# newimu.net
KiCad netlist of a schematic drawn in EAGLE
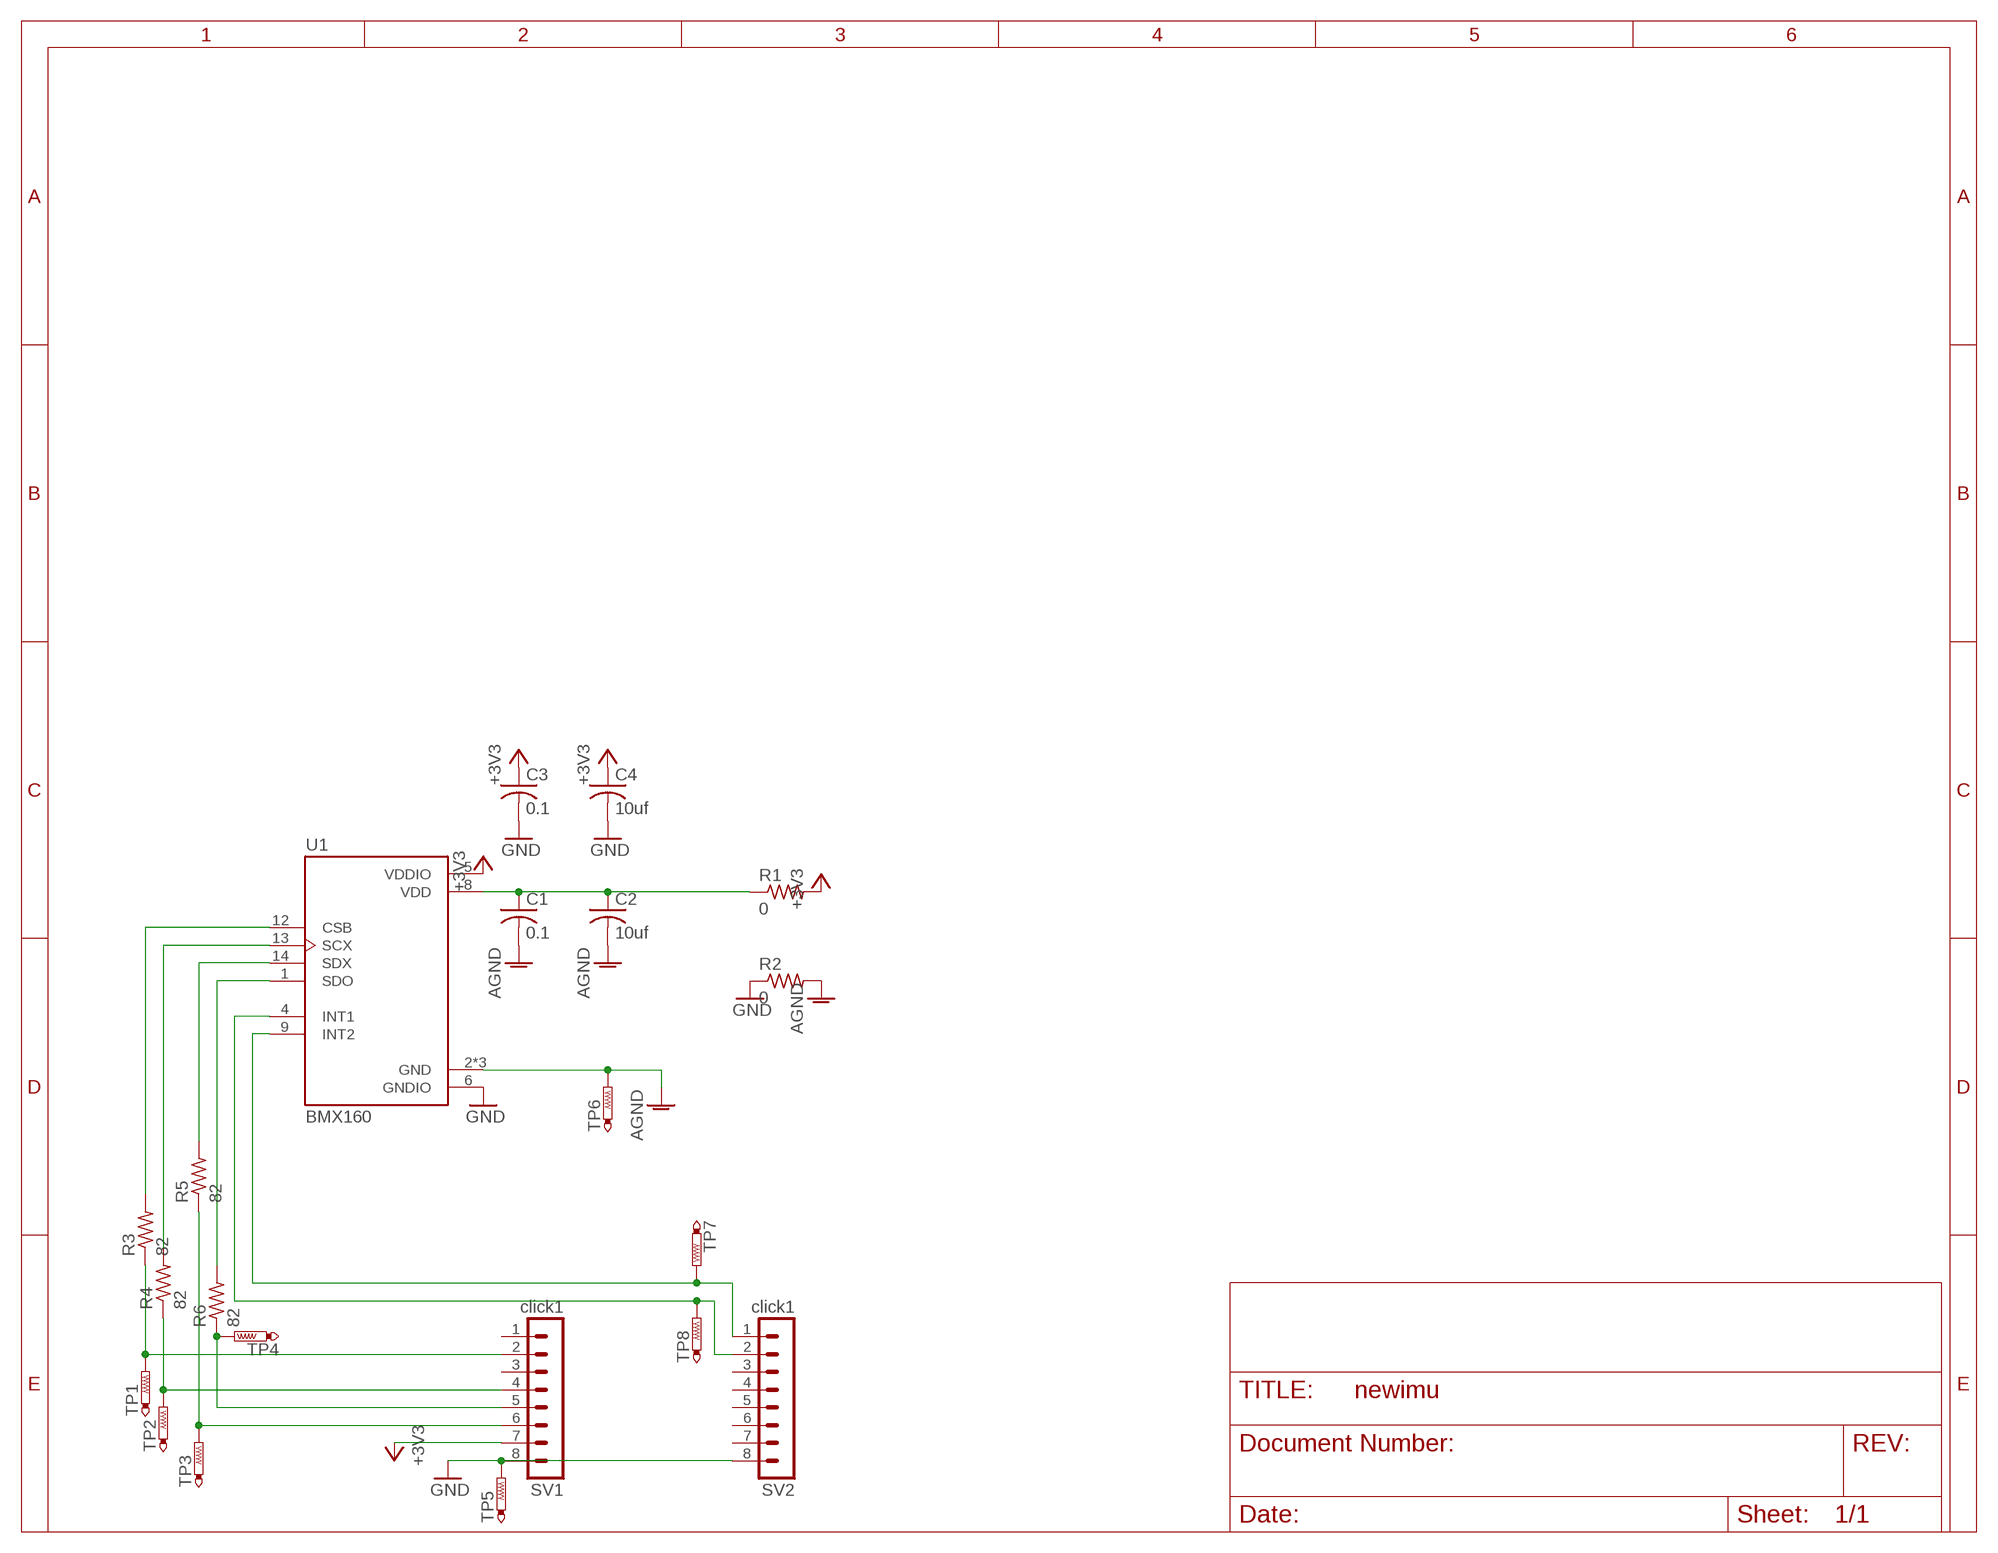
[diagram p0: schematic, sheet 1]

(export (version "E")
  (design (tool "Eeschema 10.0.6"))
  (components
    (comp (ref "C1")
      (value "0.1")
      (footprint "eagle-import:C0805")
      (libsource (lib "eagle-import") (part "C-USC0805"))
    )
    (comp (ref "C2")
      (value "10uf")
      (footprint "eagle-import:C0805")
      (libsource (lib "eagle-import") (part "C-USC0805"))
    )
    (comp (ref "C3")
      (value "0.1")
      (footprint "eagle-import:C0805")
      (libsource (lib "eagle-import") (part "C-USC0805"))
    )
    (comp (ref "C4")
      (value "10uf")
      (footprint "eagle-import:C0805")
      (libsource (lib "eagle-import") (part "C-USC0805"))
    )
    (comp (ref "R1")
      (value "0")
      (footprint "eagle-import:M0805")
      (libsource (lib "eagle-import") (part "R-US_M0805"))
    )
    (comp (ref "R2")
      (value "0")
      (footprint "eagle-import:M0805")
      (libsource (lib "eagle-import") (part "R-US_M0805"))
    )
    (comp (ref "R3")
      (value "82")
      (footprint "eagle-import:M0805")
      (libsource (lib "eagle-import") (part "R-US_M0805"))
    )
    (comp (ref "R4")
      (value "82")
      (footprint "eagle-import:M0805")
      (libsource (lib "eagle-import") (part "R-US_M0805"))
    )
    (comp (ref "R5")
      (value "82")
      (footprint "eagle-import:M0805")
      (libsource (lib "eagle-import") (part "R-US_M0805"))
    )
    (comp (ref "R6")
      (value "82")
      (footprint "eagle-import:M0805")
      (libsource (lib "eagle-import") (part "R-US_M0805"))
    )
    (comp (ref "SV1")
      (value "click1")
      (footprint "eagle-import:MA08-1")
      (libsource (lib "eagle-import") (part "MA08-1"))
    )
    (comp (ref "SV2")
      (value "click1")
      (footprint "eagle-import:MA08-1")
      (libsource (lib "eagle-import") (part "MA08-1"))
    )
    (comp (ref "TP1")
      (value "PTR1B1,27")
      (footprint "eagle-import:B1,27")
      (libsource (lib "eagle-import") (part "PTR1B1,27"))
    )
    (comp (ref "TP2")
      (value "PTR1B1,27")
      (footprint "eagle-import:B1,27")
      (libsource (lib "eagle-import") (part "PTR1B1,27"))
    )
    (comp (ref "TP3")
      (value "PTR1B1,27")
      (footprint "eagle-import:B1,27")
      (libsource (lib "eagle-import") (part "PTR1B1,27"))
    )
    (comp (ref "TP4")
      (value "PTR1B1,27")
      (footprint "eagle-import:B1,27")
      (libsource (lib "eagle-import") (part "PTR1B1,27"))
    )
    (comp (ref "TP5")
      (value "PTR1B1,27")
      (footprint "eagle-import:B1,27")
      (libsource (lib "eagle-import") (part "PTR1B1,27"))
    )
    (comp (ref "TP6")
      (value "PTR1B1,27")
      (footprint "eagle-import:B1,27")
      (libsource (lib "eagle-import") (part "PTR1B1,27"))
    )
    (comp (ref "TP7")
      (value "PTR1B1,27")
      (footprint "eagle-import:B1,27")
      (libsource (lib "eagle-import") (part "PTR1B1,27"))
    )
    (comp (ref "TP8")
      (value "PTR1B1,27")
      (footprint "eagle-import:B1,27")
      (libsource (lib "eagle-import") (part "PTR1B1,27"))
    )
    (comp (ref "U1")
      (value "BMX160")
      (footprint "eagle-import:PQFN50P250X300X100-14N")
      (fields (field (name "MF") "Bosch Sensortec"))
      (libsource (lib "eagle-import") (part "BMX160"))
    )
  )
  (nets
    (net (code "1") (name "+3V3") (class "Default")
      (node (ref "C3") (pin "1") (pinfunction "1_1") (pintype "passive"))
      (node (ref "C4") (pin "1") (pinfunction "1_1") (pintype "passive"))
      (node (ref "R1") (pin "2") (pinfunction "2_2") (pintype "passive"))
      (node (ref "SV1") (pin "7") (pinfunction "7_7") (pintype "passive"))
      (node (ref "U1") (pin "5") (pinfunction "VDDIO_5") (pintype "power_in"))
    )
    (net (code "2") (name "AGND") (class "Default")
      (node (ref "C1") (pin "2") (pinfunction "2_2") (pintype "passive"))
      (node (ref "C2") (pin "2") (pinfunction "2_2") (pintype "passive"))
      (node (ref "R2") (pin "2") (pinfunction "2_2") (pintype "passive"))
      (node (ref "TP6") (pin "TP") (pinfunction "TP_TP") (pintype "input"))
      (node (ref "U1") (pin "2") (pinfunction "GND_2") (pintype "power_in"))
      (node (ref "U1") (pin "3") (pinfunction "GND_3") (pintype "power_in"))
      (node (ref "U1") (pin "7") (pinfunction "GND_7") (pintype "power_in"))
    )
    (net (code "3") (name "GND") (class "Default")
      (node (ref "C3") (pin "2") (pinfunction "2_2") (pintype "passive"))
      (node (ref "C4") (pin "2") (pinfunction "2_2") (pintype "passive"))
      (node (ref "R2") (pin "1") (pinfunction "1_1") (pintype "passive"))
      (node (ref "SV1") (pin "8") (pinfunction "8_8") (pintype "passive"))
      (node (ref "SV2") (pin "8") (pinfunction "8_8") (pintype "passive"))
      (node (ref "TP5") (pin "TP") (pinfunction "TP_TP") (pintype "input"))
      (node (ref "U1") (pin "6") (pinfunction "GNDIO_6") (pintype "power_in"))
    )
    (net (code "4") (name "Net-(R3-Pad1)") (class "Default")
      (node (ref "R3") (pin "1") (pinfunction "1_1") (pintype "passive"))
      (node (ref "SV1") (pin "2") (pinfunction "2_2") (pintype "passive"))
      (node (ref "TP1") (pin "TP") (pinfunction "TP_TP") (pintype "input"))
    )
    (net (code "5") (name "Net-(R4-Pad1)") (class "Default")
      (node (ref "R4") (pin "1") (pinfunction "1_1") (pintype "passive"))
      (node (ref "SV1") (pin "4") (pinfunction "4_4") (pintype "passive"))
      (node (ref "TP2") (pin "TP") (pinfunction "TP_TP") (pintype "input"))
    )
    (net (code "6") (name "Net-(R5-Pad1)") (class "Default")
      (node (ref "R5") (pin "1") (pinfunction "1_1") (pintype "passive"))
      (node (ref "SV1") (pin "6") (pinfunction "6_6") (pintype "passive"))
      (node (ref "TP3") (pin "TP") (pinfunction "TP_TP") (pintype "input"))
    )
    (net (code "7") (name "Net-(R6-Pad1)") (class "Default")
      (node (ref "R6") (pin "1") (pinfunction "1_1") (pintype "passive"))
      (node (ref "SV1") (pin "5") (pinfunction "5_5") (pintype "passive"))
      (node (ref "TP4") (pin "TP") (pinfunction "TP_TP") (pintype "input"))
    )
    (net (code "8") (name "Net-(U1-CSB)") (class "Default")
      (node (ref "R3") (pin "2") (pinfunction "2_2") (pintype "passive"))
      (node (ref "U1") (pin "12") (pinfunction "CSB_12") (pintype "input"))
    )
    (net (code "9") (name "Net-(U1-INT1)") (class "Default")
      (node (ref "SV2") (pin "2") (pinfunction "2_2") (pintype "passive"))
      (node (ref "TP8") (pin "TP") (pinfunction "TP_TP") (pintype "input"))
      (node (ref "U1") (pin "4") (pinfunction "INT1_4") (pintype "bidirectional"))
    )
    (net (code "10") (name "Net-(U1-INT2)") (class "Default")
      (node (ref "SV2") (pin "1") (pinfunction "1_1") (pintype "passive"))
      (node (ref "TP7") (pin "TP") (pinfunction "TP_TP") (pintype "input"))
      (node (ref "U1") (pin "9") (pinfunction "INT2_9") (pintype "bidirectional"))
    )
    (net (code "11") (name "Net-(U1-SCX)") (class "Default")
      (node (ref "R4") (pin "2") (pinfunction "2_2") (pintype "passive"))
      (node (ref "U1") (pin "13") (pinfunction "SCX_13") (pintype "input"))
    )
    (net (code "12") (name "Net-(U1-SDO)") (class "Default")
      (node (ref "R6") (pin "2") (pinfunction "2_2") (pintype "passive"))
      (node (ref "U1") (pin "1") (pinfunction "SDO_1") (pintype "bidirectional"))
    )
    (net (code "13") (name "Net-(U1-SDX)") (class "Default")
      (node (ref "R5") (pin "2") (pinfunction "2_2") (pintype "passive"))
      (node (ref "U1") (pin "14") (pinfunction "SDX_14") (pintype "bidirectional"))
    )
    (net (code "14") (name "Net-(U1-VDD)") (class "Default")
      (node (ref "C1") (pin "1") (pinfunction "1_1") (pintype "passive"))
      (node (ref "C2") (pin "1") (pinfunction "1_1") (pintype "passive"))
      (node (ref "R1") (pin "1") (pinfunction "1_1") (pintype "passive"))
      (node (ref "U1") (pin "8") (pinfunction "VDD_8") (pintype "power_in"))
    )
    (net (code "15") (name "unconnected-(SV1-Pad1)") (class "Default")
      (node (ref "SV1") (pin "1") (pinfunction "1_1") (pintype "passive"))
    )
    (net (code "16") (name "unconnected-(SV1-Pad3)") (class "Default")
      (node (ref "SV1") (pin "3") (pinfunction "3_3") (pintype "passive"))
    )
    (net (code "17") (name "unconnected-(SV2-Pad3)") (class "Default")
      (node (ref "SV2") (pin "3") (pinfunction "3_3") (pintype "passive"))
    )
    (net (code "18") (name "unconnected-(SV2-Pad4)") (class "Default")
      (node (ref "SV2") (pin "4") (pinfunction "4_4") (pintype "passive"))
    )
    (net (code "19") (name "unconnected-(SV2-Pad5)") (class "Default")
      (node (ref "SV2") (pin "5") (pinfunction "5_5") (pintype "passive"))
    )
    (net (code "20") (name "unconnected-(SV2-Pad6)") (class "Default")
      (node (ref "SV2") (pin "6") (pinfunction "6_6") (pintype "passive"))
    )
    (net (code "21") (name "unconnected-(SV2-Pad7)") (class "Default")
      (node (ref "SV2") (pin "7") (pinfunction "7_7") (pintype "passive"))
    )
  )
)
